# mp3431-boost-tester-mk-1_0_0.net
KiCad netlist of a schematic drawn in EAGLE
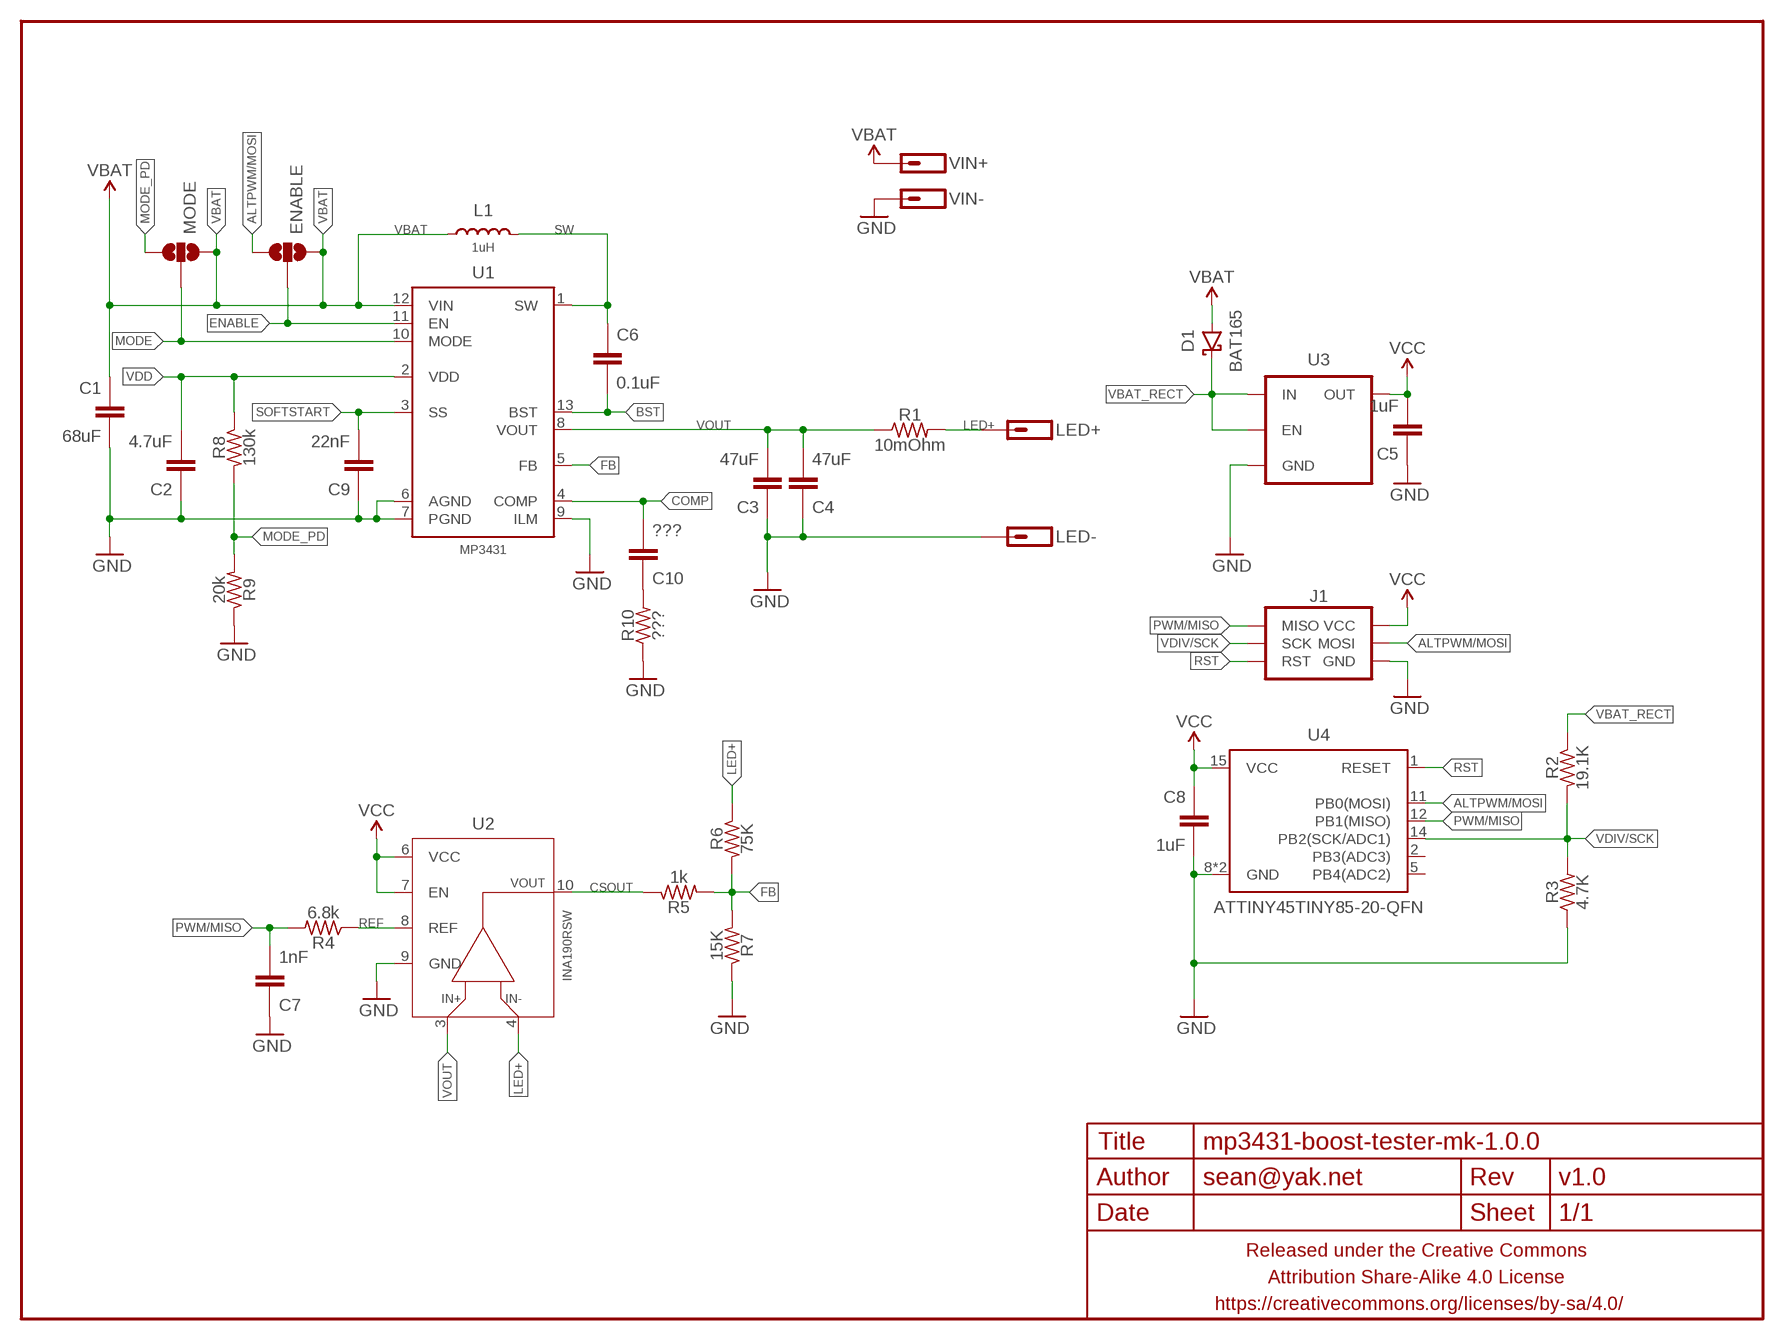
[diagram p0: schematic, sheet 1]

(export (version "E")
  (design (tool "Eeschema 10.0.6"))
  (components
    (comp (ref "C1")
      (value "68uF")
      (footprint "eagle-import:C1206")
      (libsource (lib "eagle-import") (part "CAPACITOR-CERAMICC1206"))
    )
    (comp (ref "C2")
      (value "4.7uF")
      (footprint "eagle-import:C0402")
      (libsource (lib "eagle-import") (part "CAPACITOR-CERAMICC0402"))
    )
    (comp (ref "C3")
      (value "47uF")
      (footprint "eagle-import:C1206")
      (libsource (lib "eagle-import") (part "CAPACITOR-CERAMICC1206"))
    )
    (comp (ref "C4")
      (value "47uF")
      (footprint "eagle-import:C1206")
      (libsource (lib "eagle-import") (part "CAPACITOR-CERAMICC1206"))
    )
    (comp (ref "C5")
      (value "1uF")
      (footprint "eagle-import:C0402")
      (libsource (lib "eagle-import") (part "CAPACITOR-CERAMICC0402"))
    )
    (comp (ref "C6")
      (value "0.1uF")
      (footprint "eagle-import:C0402")
      (libsource (lib "eagle-import") (part "CAPACITOR-CERAMICC0402"))
    )
    (comp (ref "C7")
      (value "1nF")
      (footprint "eagle-import:C0402")
      (libsource (lib "eagle-import") (part "CAPACITOR-CERAMICC0402"))
    )
    (comp (ref "C8")
      (value "1uF")
      (footprint "eagle-import:C0402")
      (libsource (lib "eagle-import") (part "CAPACITOR-CERAMICC0402"))
    )
    (comp (ref "C9")
      (value "22nF")
      (footprint "eagle-import:C0402")
      (libsource (lib "eagle-import") (part "CAPACITOR-CERAMICC0402"))
    )
    (comp (ref "C10")
      (value "???")
      (footprint "eagle-import:C0402")
      (libsource (lib "eagle-import") (part "CAPACITOR-CERAMICC0402"))
    )
    (comp (ref "D1")
      (value "BAT165")
      (footprint "eagle-import:SOD323-SCHOTTKY")
      (libsource (lib "eagle-import") (part "DIODE-SCHOTTKYSOD323"))
    )
    (comp (ref "ENABLE")
      (value "JUMPER-PAD-3-NOSMALL_BOX_SILK")
      (footprint "eagle-import:PAD-JUMPER-3-NO_YES_SILK_SMALL_BOX")
      (libsource (lib "eagle-import") (part "JUMPER-PAD-3-NOSMALL_BOX_SILK"))
    )
    (comp (ref "FRAME1")
      (value "FRAME-LETTERNO_PACKAGE")
      (footprint "eagle-import:DUMMY")
      (fields
        (field (name "DESIGNER") "Nobody")
        (field (name "VERSION") "v01")
        (field (name "DESIGNER_1") "sean@yak.net")
        (field (name "VERSION_1") "v1.0")
      )
      (libsource (lib "eagle-import") (part "FRAME-LETTERNO_PACKAGE"))
    )
    (comp (ref "J1")
      (value "AVR_SPI_PRG_6SMD-1.27MM")
      (footprint "eagle-import:2X3-1.27MM-SMD")
      (libsource (lib "eagle-import") (part "AVR_SPI_PRG_6SMD-1.27MM"))
    )
    (comp (ref "L1")
      (value "1uH")
      (footprint "eagle-import:XAL7070")
      (libsource (lib "eagle-import") (part "INDUCTORXAL7070"))
    )
    (comp (ref "LED+")
      (value "M01PTH-1.2MM-NS")
      (footprint "eagle-import:1X01-1.2MM-NS")
      (libsource (lib "eagle-import") (part "M01PTH-1.2MM-NS"))
    )
    (comp (ref "LED-")
      (value "M01PTH-1.2MM-NS")
      (footprint "eagle-import:1X01-1.2MM-NS")
      (libsource (lib "eagle-import") (part "M01PTH-1.2MM-NS"))
    )
    (comp (ref "MODE")
      (value "JUMPER-PAD-3-NOSMALL_BOX_SILK")
      (footprint "eagle-import:PAD-JUMPER-3-NO_YES_SILK_SMALL_BOX")
      (libsource (lib "eagle-import") (part "JUMPER-PAD-3-NOSMALL_BOX_SILK"))
    )
    (comp (ref "R1")
      (value "10mOhm")
      (footprint "eagle-import:R1206")
      (libsource (lib "eagle-import") (part "RESISTORR1206"))
    )
    (comp (ref "R2")
      (value "19.1K")
      (footprint "eagle-import:R0402")
      (libsource (lib "eagle-import") (part "RESISTORR0402"))
    )
    (comp (ref "R3")
      (value "4.7K")
      (footprint "eagle-import:R0402")
      (libsource (lib "eagle-import") (part "RESISTORR0402"))
    )
    (comp (ref "R4")
      (value "6.8k")
      (footprint "eagle-import:R0402")
      (libsource (lib "eagle-import") (part "RESISTORR0402"))
    )
    (comp (ref "R5")
      (value "1k")
      (footprint "eagle-import:R0402")
      (libsource (lib "eagle-import") (part "RESISTORR0402"))
    )
    (comp (ref "R6")
      (value "75K")
      (footprint "eagle-import:R0402")
      (libsource (lib "eagle-import") (part "RESISTORR0402"))
    )
    (comp (ref "R7")
      (value "15K")
      (footprint "eagle-import:R0402")
      (libsource (lib "eagle-import") (part "RESISTORR0402"))
    )
    (comp (ref "R8")
      (value "130k")
      (footprint "eagle-import:R0402")
      (libsource (lib "eagle-import") (part "RESISTORR0402"))
    )
    (comp (ref "R9")
      (value "20k")
      (footprint "eagle-import:R0402")
      (libsource (lib "eagle-import") (part "RESISTORR0402"))
    )
    (comp (ref "R10")
      (value "???")
      (footprint "eagle-import:R0402")
      (libsource (lib "eagle-import") (part "RESISTORR0402"))
    )
    (comp (ref "U1")
      (value "MP3431")
      (footprint "eagle-import:MP3431")
      (libsource (lib "eagle-import") (part "MP3431"))
    )
    (comp (ref "U2")
      (value "INA190RSW")
      (footprint "eagle-import:UQFN-10")
      (libsource (lib "eagle-import") (part "INA190RSW"))
    )
    (comp (ref "U3")
      (value "V_REG_ENTLV700")
      (footprint "eagle-import:SC70")
      (libsource (lib "eagle-import") (part "V_REG_ENTLV700"))
    )
    (comp (ref "U4")
      (value "ATTINY45TINY85-20-QFN")
      (footprint "eagle-import:QFN20")
      (libsource (lib "eagle-import") (part "ATTINY45TINY85-20-QFN"))
    )
    (comp (ref "VIN+")
      (value "M01PTH-1.2MM-NS")
      (footprint "eagle-import:1X01-1.2MM-NS")
      (libsource (lib "eagle-import") (part "M01PTH-1.2MM-NS"))
    )
    (comp (ref "VIN-")
      (value "M01PTH-1.2MM-NS")
      (footprint "eagle-import:1X01-1.2MM-NS")
      (libsource (lib "eagle-import") (part "M01PTH-1.2MM-NS"))
    )
  )
  (nets
    (net (code "1") (name "/CSOUT") (class "Default")
      (node (ref "R5") (pin "1") (pinfunction "1_1") (pintype "passive"))
      (node (ref "U2") (pin "10") (pinfunction "OUT_10") (pintype "bidirectional"))
    )
    (net (code "2") (name "/REF") (class "Default")
      (node (ref "R4") (pin "1") (pinfunction "1_1") (pintype "passive"))
      (node (ref "U2") (pin "8") (pinfunction "REF_8") (pintype "bidirectional"))
    )
    (net (code "3") (name "/SW") (class "Default")
      (node (ref "C6") (pin "1") (pinfunction "1_1") (pintype "passive"))
      (node (ref "L1") (pin "P$2") (pinfunction "2_P$2") (pintype "passive"))
      (node (ref "U1") (pin "1") (pinfunction "SW_1") (pintype "bidirectional"))
    )
    (net (code "4") (name "ALTPWM{slash}MOSI") (class "Default")
      (node (ref "ENABLE") (pin "3") (pinfunction "3_3") (pintype "passive"))
      (node (ref "J1") (pin "4") (pinfunction "MOSI_4") (pintype "passive"))
      (node (ref "U4") (pin "11") (pinfunction "PB0(MOSI)_11") (pintype "bidirectional"))
    )
    (net (code "5") (name "BST") (class "Default")
      (node (ref "C6") (pin "2") (pinfunction "2_2") (pintype "passive"))
      (node (ref "U1") (pin "13") (pinfunction "BST_13") (pintype "bidirectional"))
    )
    (net (code "6") (name "COMP") (class "Default")
      (node (ref "C10") (pin "2") (pinfunction "2_2") (pintype "passive"))
      (node (ref "U1") (pin "4") (pinfunction "COMP_4") (pintype "bidirectional"))
    )
    (net (code "7") (name "ENABLE") (class "Default")
      (node (ref "ENABLE") (pin "2") (pinfunction "2_2") (pintype "passive"))
      (node (ref "U1") (pin "11") (pinfunction "EN_11") (pintype "bidirectional"))
    )
    (net (code "8") (name "FB") (class "Default")
      (node (ref "R5") (pin "2") (pinfunction "2_2") (pintype "passive"))
      (node (ref "R6") (pin "2") (pinfunction "2_2") (pintype "passive"))
      (node (ref "R7") (pin "2") (pinfunction "2_2") (pintype "passive"))
      (node (ref "U1") (pin "5") (pinfunction "FB_5") (pintype "bidirectional"))
    )
    (net (code "9") (name "GND") (class "Default")
      (node (ref "C1") (pin "2") (pinfunction "2_2") (pintype "passive"))
      (node (ref "C2") (pin "1") (pinfunction "1_1") (pintype "passive"))
      (node (ref "C3") (pin "1") (pinfunction "1_1") (pintype "passive"))
      (node (ref "C4") (pin "1") (pinfunction "1_1") (pintype "passive"))
      (node (ref "C5") (pin "1") (pinfunction "1_1") (pintype "passive"))
      (node (ref "C7") (pin "1") (pinfunction "1_1") (pintype "passive"))
      (node (ref "C8") (pin "2") (pinfunction "2_2") (pintype "passive"))
      (node (ref "C9") (pin "1") (pinfunction "1_1") (pintype "passive"))
      (node (ref "J1") (pin "6") (pinfunction "GND_6") (pintype "passive"))
      (node (ref "LED-") (pin "P$1") (pinfunction "1_P$1") (pintype "passive"))
      (node (ref "R10") (pin "1") (pinfunction "1_1") (pintype "passive"))
      (node (ref "R3") (pin "1") (pinfunction "1_1") (pintype "passive"))
      (node (ref "R7") (pin "1") (pinfunction "1_1") (pintype "passive"))
      (node (ref "R9") (pin "1") (pinfunction "1_1") (pintype "passive"))
      (node (ref "U1") (pin "6") (pinfunction "AGND_6") (pintype "bidirectional"))
      (node (ref "U1") (pin "7") (pinfunction "PGND_7") (pintype "bidirectional"))
      (node (ref "U1") (pin "9") (pinfunction "ILM_9") (pintype "bidirectional"))
      (node (ref "U2") (pin "9") (pinfunction "GND_9") (pintype "bidirectional"))
      (node (ref "U3") (pin "2") (pinfunction "GND_2") (pintype "input"))
      (node (ref "U4") (pin "8") (pinfunction "GND_8") (pintype "bidirectional"))
      (node (ref "U4") (pin "PAD") (pinfunction "GND_PAD") (pintype "bidirectional"))
      (node (ref "VIN-") (pin "P$1") (pinfunction "1_P$1") (pintype "passive"))
    )
    (net (code "10") (name "LED+") (class "Default")
      (node (ref "LED+") (pin "P$1") (pinfunction "1_P$1") (pintype "passive"))
      (node (ref "R1") (pin "2") (pinfunction "2_2") (pintype "passive"))
      (node (ref "R6") (pin "1") (pinfunction "1_1") (pintype "passive"))
      (node (ref "U2") (pin "4") (pinfunction "VIN-_4") (pintype "bidirectional"))
    )
    (net (code "11") (name "MODE") (class "Default")
      (node (ref "MODE") (pin "2") (pinfunction "2_2") (pintype "passive"))
      (node (ref "U1") (pin "10") (pinfunction "MODE_10") (pintype "bidirectional"))
    )
    (net (code "12") (name "MODE_PD") (class "Default")
      (node (ref "MODE") (pin "3") (pinfunction "3_3") (pintype "passive"))
      (node (ref "R8") (pin "2") (pinfunction "2_2") (pintype "passive"))
      (node (ref "R9") (pin "2") (pinfunction "2_2") (pintype "passive"))
    )
    (net (code "13") (name "Net-(C10-Pad1)") (class "Default")
      (node (ref "C10") (pin "1") (pinfunction "1_1") (pintype "passive"))
      (node (ref "R10") (pin "2") (pinfunction "2_2") (pintype "passive"))
    )
    (net (code "14") (name "PWM{slash}MISO") (class "Default")
      (node (ref "C7") (pin "2") (pinfunction "2_2") (pintype "passive"))
      (node (ref "J1") (pin "1") (pinfunction "MISO_1") (pintype "passive"))
      (node (ref "R4") (pin "2") (pinfunction "2_2") (pintype "passive"))
      (node (ref "U4") (pin "12") (pinfunction "PB1(MISO)_12") (pintype "bidirectional"))
    )
    (net (code "15") (name "RST") (class "Default")
      (node (ref "J1") (pin "5") (pinfunction "RST_5") (pintype "passive"))
      (node (ref "U4") (pin "1") (pinfunction "RESET_1") (pintype "bidirectional"))
    )
    (net (code "16") (name "SOFTSTART") (class "Default")
      (node (ref "C9") (pin "2") (pinfunction "2_2") (pintype "passive"))
      (node (ref "U1") (pin "3") (pinfunction "SS_3") (pintype "bidirectional"))
    )
    (net (code "17") (name "VBAT") (class "Default")
      (node (ref "C1") (pin "1") (pinfunction "1_1") (pintype "passive"))
      (node (ref "D1") (pin "A") (pinfunction "A_A") (pintype "passive"))
      (node (ref "ENABLE") (pin "1") (pinfunction "1_1") (pintype "passive"))
      (node (ref "L1") (pin "P$1") (pinfunction "1_P$1") (pintype "passive"))
      (node (ref "MODE") (pin "1") (pinfunction "1_1") (pintype "passive"))
      (node (ref "U1") (pin "12") (pinfunction "VIN_12") (pintype "bidirectional"))
      (node (ref "VIN+") (pin "P$1") (pinfunction "1_P$1") (pintype "passive"))
    )
    (net (code "18") (name "VBAT_RECT") (class "Default")
      (node (ref "D1") (pin "C") (pinfunction "C_C") (pintype "passive"))
      (node (ref "R2") (pin "1") (pinfunction "1_1") (pintype "passive"))
      (node (ref "U3") (pin "1") (pinfunction "IN_1") (pintype "input"))
      (node (ref "U3") (pin "3") (pinfunction "EN_3") (pintype "input"))
    )
    (net (code "19") (name "VCC") (class "Default")
      (node (ref "C5") (pin "2") (pinfunction "2_2") (pintype "passive"))
      (node (ref "C8") (pin "1") (pinfunction "1_1") (pintype "passive"))
      (node (ref "J1") (pin "2") (pinfunction "VCC_2") (pintype "passive"))
      (node (ref "U2") (pin "6") (pinfunction "VCC_6") (pintype "bidirectional"))
      (node (ref "U2") (pin "7") (pinfunction "EN_7") (pintype "bidirectional"))
      (node (ref "U3") (pin "5") (pinfunction "OUT_5") (pintype "passive"))
      (node (ref "U4") (pin "15") (pinfunction "VCC_15") (pintype "bidirectional"))
    )
    (net (code "20") (name "VDD") (class "Default")
      (node (ref "C2") (pin "2") (pinfunction "2_2") (pintype "passive"))
      (node (ref "R8") (pin "1") (pinfunction "1_1") (pintype "passive"))
      (node (ref "U1") (pin "2") (pinfunction "VDD_2") (pintype "bidirectional"))
    )
    (net (code "21") (name "VDIV{slash}SCK") (class "Default")
      (node (ref "J1") (pin "3") (pinfunction "SCK_3") (pintype "passive"))
      (node (ref "R2") (pin "2") (pinfunction "2_2") (pintype "passive"))
      (node (ref "R3") (pin "2") (pinfunction "2_2") (pintype "passive"))
      (node (ref "U4") (pin "14") (pinfunction "PB2(SCK/ADC1)_14") (pintype "bidirectional"))
    )
    (net (code "22") (name "VOUT") (class "Default")
      (node (ref "C3") (pin "2") (pinfunction "2_2") (pintype "passive"))
      (node (ref "C4") (pin "2") (pinfunction "2_2") (pintype "passive"))
      (node (ref "R1") (pin "1") (pinfunction "1_1") (pintype "passive"))
      (node (ref "U1") (pin "8") (pinfunction "VOUT_8") (pintype "bidirectional"))
      (node (ref "U2") (pin "3") (pinfunction "VIN+_3") (pintype "bidirectional"))
    )
    (net (code "23") (name "unconnected-(U4-PB3(ADC3)-Pad2)") (class "Default")
      (node (ref "U4") (pin "2") (pinfunction "PB3(ADC3)_2") (pintype "bidirectional"))
    )
    (net (code "24") (name "unconnected-(U4-PB4(ADC2)-Pad5)") (class "Default")
      (node (ref "U4") (pin "5") (pinfunction "PB4(ADC2)_5") (pintype "bidirectional"))
    )
  )
)
